# SCH_Card_2024-08-03.net
KiCad netlist of a schematic drawn in EasyEDA
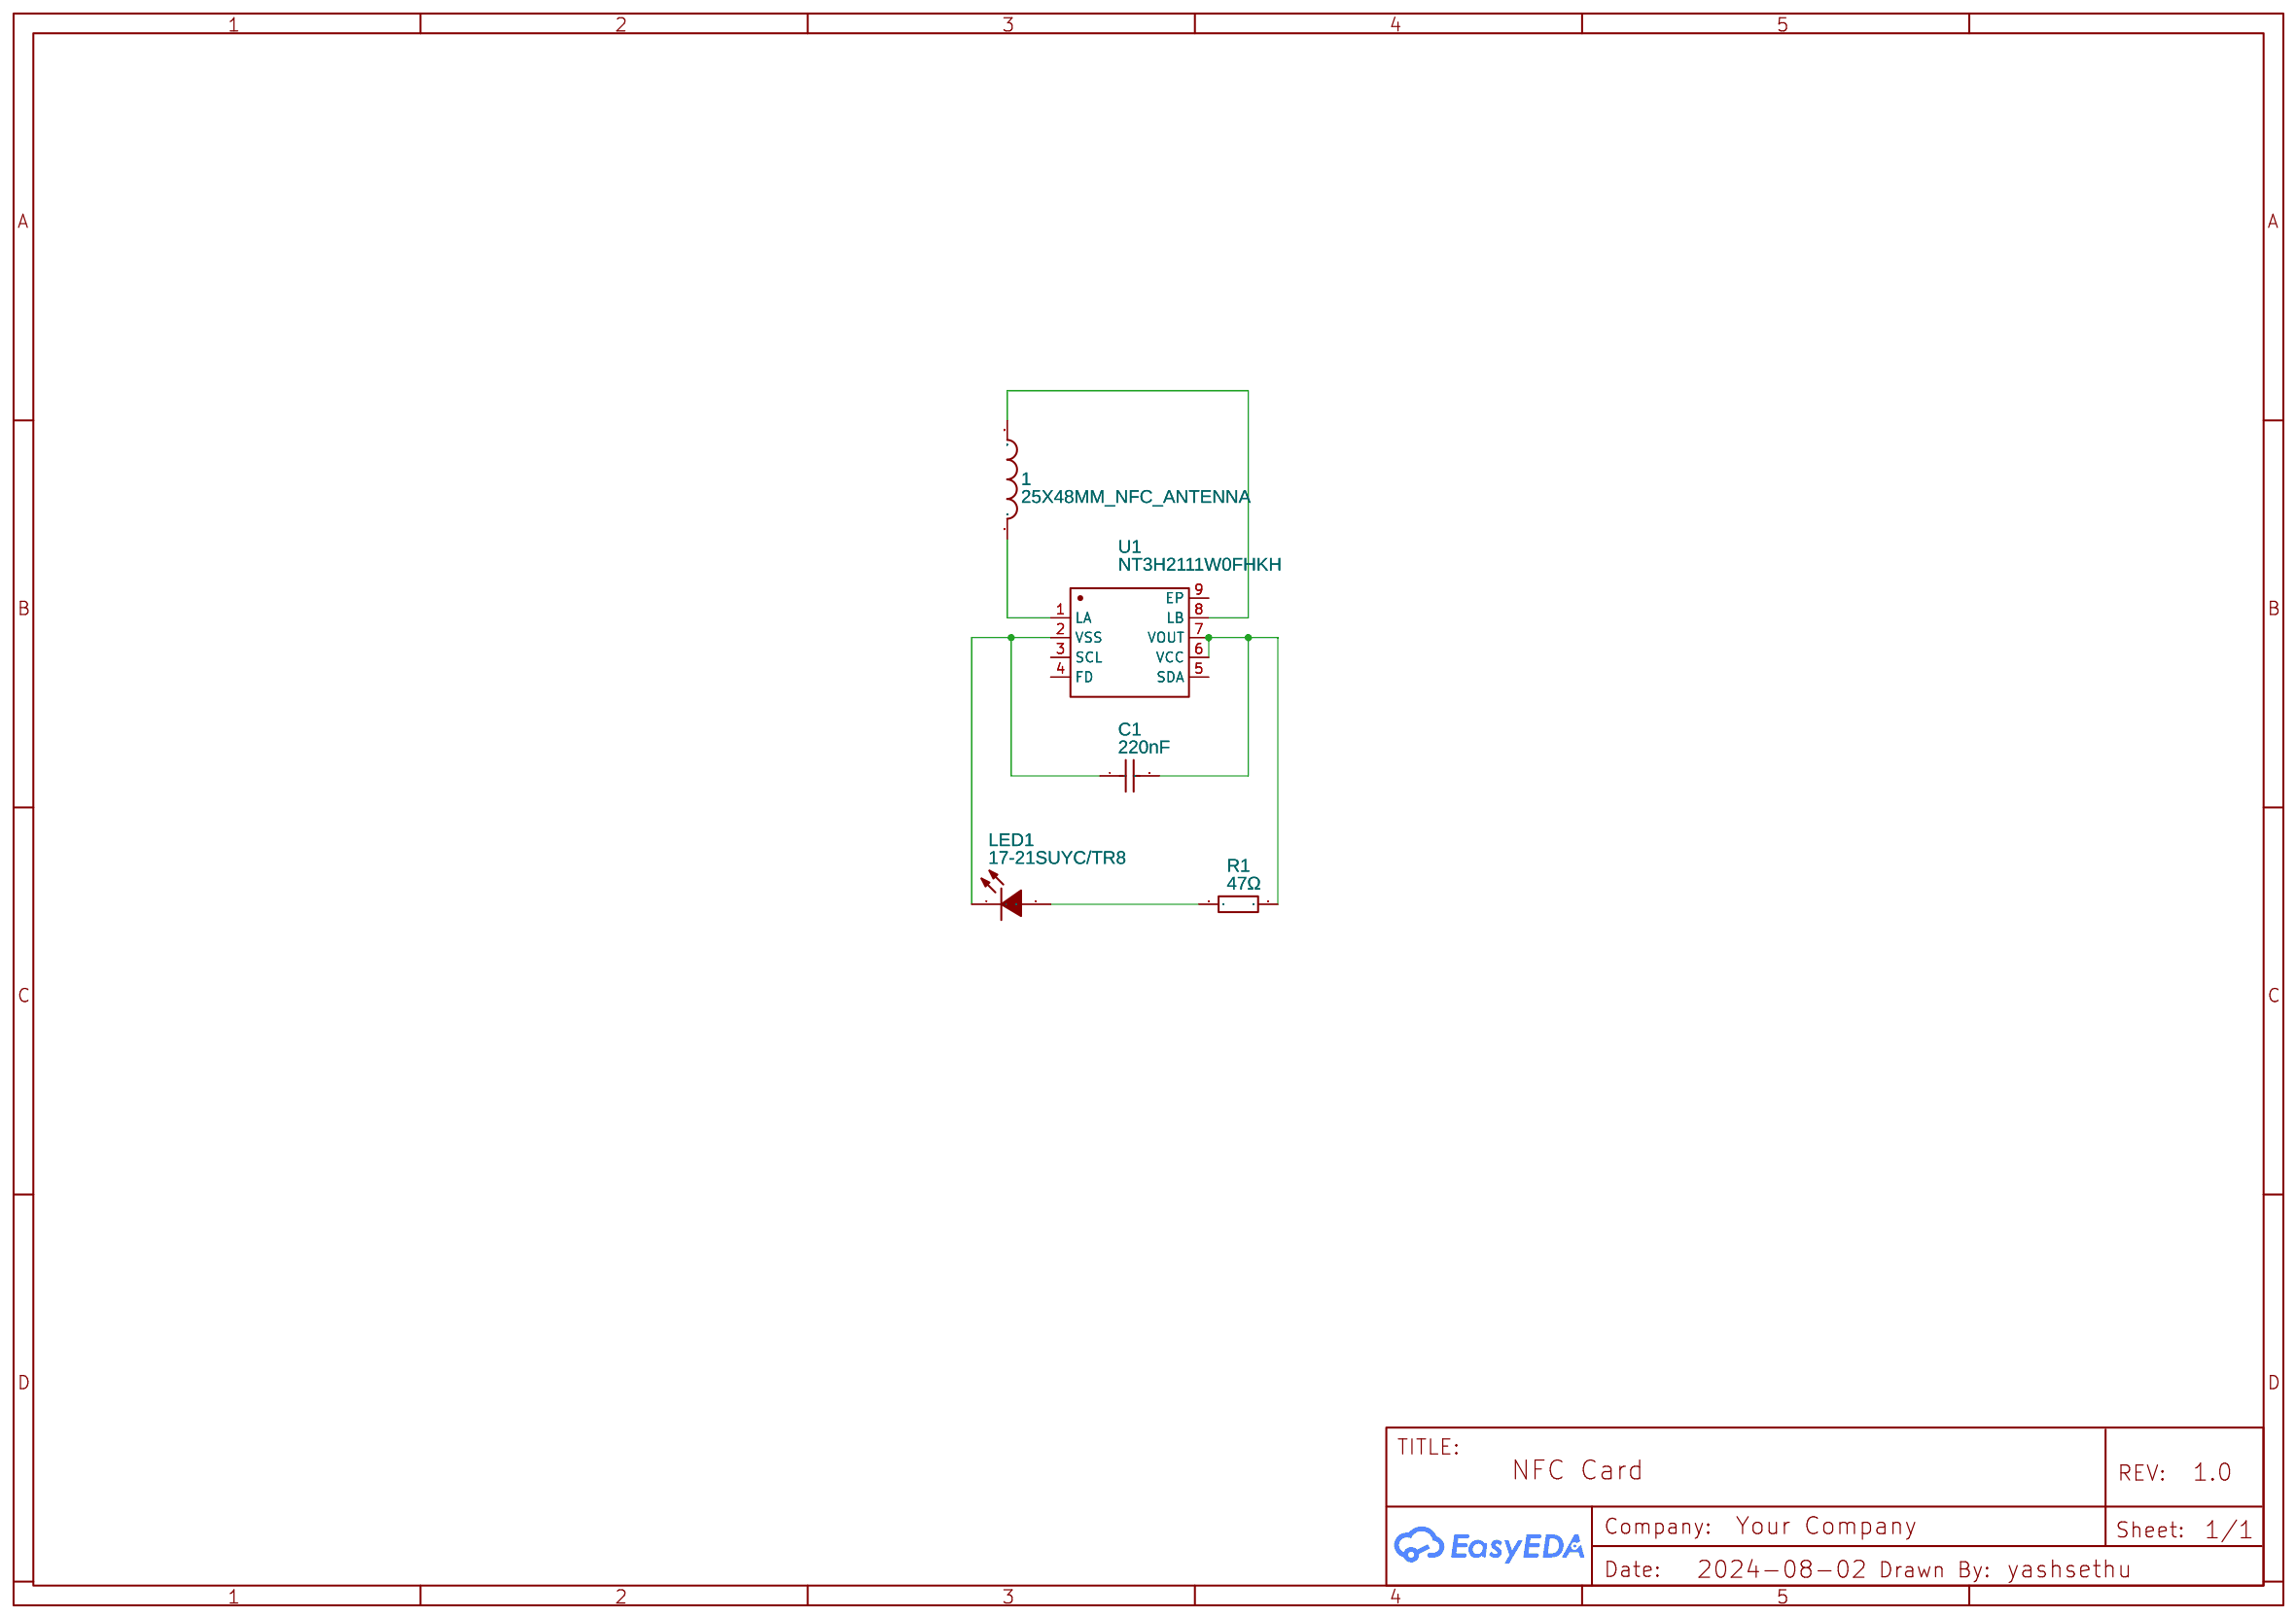
[diagram p0: schematic sheet]

(export (version "E")
  (design (tool "Eeschema 10.0.6"))
  (components
    (comp (ref "1") (value "25X48MM_NFC_ANTENNA") (libsource (lib "") (part "25X48MM_NFC_ANTENNA")))
    (comp (ref "C1")
      (value "220nF")
      (fields
        (field (name "Manufacturer Part") "CL10B224KA8NNNC")
        (field (name "Manufacturer") "SAMSUNG(三星)")
      )
      (libsource (lib "") (part "CL10B224KA8NNNC"))
    )
    (comp (ref "LED1")
      (value "17-21SUYC/TR8")
      (fields (field (name "Manufacturer Part") "KT-0805黄灯") (field (name "Manufacturer") "KENTO"))
      (libsource (lib "") (part "17-21SUYC/TR8"))
    )
    (comp (ref "R1")
      (value "47Ω")
      (fields
        (field (name "Manufacturer Part") "0603WAF470JT5E")
        (field (name "Manufacturer") "UNI-ROYAL(厚声)")
      )
      (libsource (lib "") (part "0603WAF470JT5E"))
    )
    (comp (ref "U1")
      (value "NT3H2111W0FHKH")
      (fields (field (name "Manufacturer") "NXP(恩智浦)"))
      (libsource (lib "") (part "NT3H2111W0FHKH"))
    )
  )
  (nets
    (net (code "1") (name "Net-(LED1-+)") (class "Default")
      (node (ref "LED1") (pin "1") (pinfunction "+_1") (pintype "unspecified"))
      (node (ref "R1") (pin "1") (pinfunction "1_1") (pintype "input"))
    )
    (net (code "2") (name "Net-(LED1--)") (class "Default")
      (node (ref "C1") (pin "1") (pinfunction "1_1") (pintype "input"))
      (node (ref "LED1") (pin "2") (pinfunction "-_2") (pintype "unspecified"))
      (node (ref "U1") (pin "2") (pinfunction "VSS_2") (pintype "unspecified"))
    )
    (net (code "3") (name "Net-(U1-LA)") (class "Default")
      (node (ref "1") (pin "P$2") (pinfunction "P$2_P$2") (pintype "bidirectional"))
      (node (ref "U1") (pin "1") (pinfunction "LA_1") (pintype "unspecified"))
    )
    (net (code "4") (name "Net-(U1-LB)") (class "Default")
      (node (ref "1") (pin "P$1") (pinfunction "P$1_P$1") (pintype "bidirectional"))
      (node (ref "U1") (pin "8") (pinfunction "LB_8") (pintype "unspecified"))
    )
    (net (code "5") (name "Net-(U1-VCC)") (class "Default")
      (node (ref "C1") (pin "2") (pinfunction "2_2") (pintype "input"))
      (node (ref "R1") (pin "2") (pinfunction "2_2") (pintype "input"))
      (node (ref "U1") (pin "6") (pinfunction "VCC_6") (pintype "unspecified"))
      (node (ref "U1") (pin "7") (pinfunction "VOUT_7") (pintype "unspecified"))
    )
    (net (code "6") (name "unconnected-(U1-EP-Pad9)") (class "Default")
      (node (ref "U1") (pin "9") (pinfunction "EP_9") (pintype "unspecified"))
    )
    (net (code "7") (name "unconnected-(U1-FD-Pad4)") (class "Default")
      (node (ref "U1") (pin "4") (pinfunction "FD_4") (pintype "unspecified"))
    )
    (net (code "8") (name "unconnected-(U1-SCL-Pad3)") (class "Default")
      (node (ref "U1") (pin "3") (pinfunction "SCL_3") (pintype "unspecified"))
    )
    (net (code "9") (name "unconnected-(U1-SDA-Pad5)") (class "Default")
      (node (ref "U1") (pin "5") (pinfunction "SDA_5") (pintype "unspecified"))
    )
  )
)
